# Termocouple.net
KiCad netlist of a schematic drawn in EAGLE
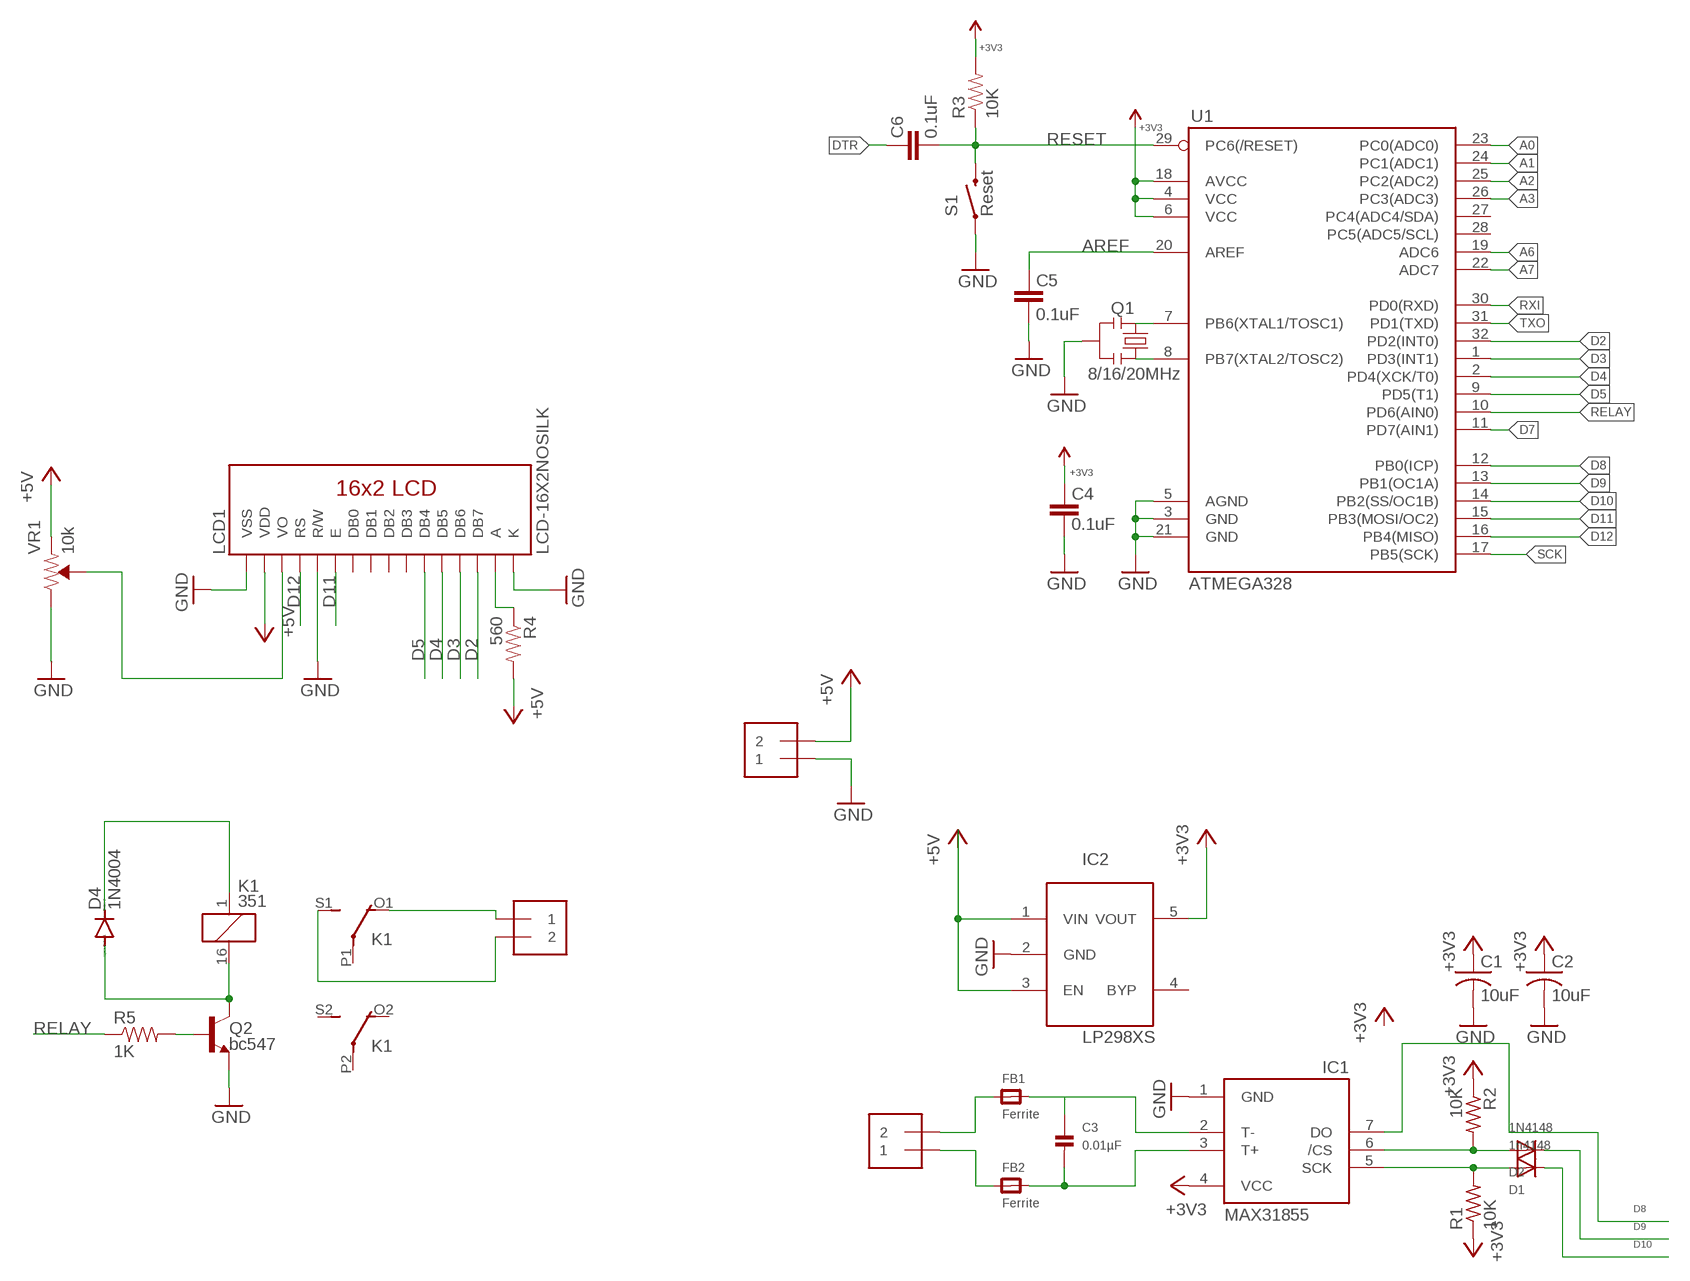
[diagram p0: schematic, sheet 1]

(export (version "E")
  (design (tool "Eeschema 10.0.6"))
  (components
    (comp (ref "C1")
      (value "10uF")
      (footprint "eagle-import:C0805K")
      (libsource (lib "eagle-import") (part "C-USC0805K"))
    )
    (comp (ref "C2")
      (value "10uF")
      (footprint "eagle-import:C0805K")
      (libsource (lib "eagle-import") (part "C-USC0805K"))
    )
    (comp (ref "C3")
      (value "0.01µF")
      (footprint "eagle-import:_0805")
      (libsource (lib "eagle-import") (part "CAP_CERAMIC_0805"))
    )
    (comp (ref "C4")
      (value "0.1uF")
      (footprint "eagle-import:0603-CAP")
      (libsource (lib "eagle-import") (part "CAP0603-CAP"))
    )
    (comp (ref "C5")
      (value "0.1uF")
      (footprint "eagle-import:0603-CAP")
      (libsource (lib "eagle-import") (part "CAP0603-CAP"))
    )
    (comp (ref "C6")
      (value "0.1uF")
      (footprint "eagle-import:0603-CAP")
      (libsource (lib "eagle-import") (part "CAP0603-CAP"))
    )
    (comp (ref "D1")
      (value "1n4148")
      (footprint "eagle-import:SOD-323F")
      (libsource (lib "eagle-import") (part "DIODESOD-323F"))
    )
    (comp (ref "D2")
      (value "1N4148")
      (footprint "eagle-import:SOD-323F")
      (libsource (lib "eagle-import") (part "DIODESOD-323F"))
    )
    (comp (ref "D4")
      (value "1N4004")
      (footprint "eagle-import:DO41-10")
      (libsource (lib "eagle-import") (part "1N4004"))
    )
    (comp (ref "FB1")
      (value "Ferrite")
      (footprint "eagle-import:_0805")
      (libsource (lib "eagle-import") (part "FERRITE_0805"))
    )
    (comp (ref "FB2")
      (value "Ferrite")
      (footprint "eagle-import:_0805")
      (libsource (lib "eagle-import") (part "FERRITE_0805"))
    )
    (comp (ref "IC1")
      (value "MAX31855")
      (footprint "eagle-import:SO08")
      (libsource (lib "eagle-import") (part "MAX6675"))
    )
    (comp (ref "IC2")
      (value "LP298XS")
      (footprint "eagle-import:SOT23-5L")
      (libsource (lib "eagle-import") (part "LP298XS"))
    )
    (comp (ref "J1")
      (value "1X2-3.5MM")
      (footprint "eagle-import:1X2-3.5MM")
      (libsource (lib "eagle-import") (part "1X2-3.5MM"))
    )
    (comp (ref "J2")
      (value "1X2-3.5MM")
      (footprint "eagle-import:1X2-3.5MM")
      (libsource (lib "eagle-import") (part "1X2-3.5MM"))
    )
    (comp (ref "J3")
      (value "1X2-3.5MM")
      (footprint "eagle-import:1X2-3.5MM")
      (libsource (lib "eagle-import") (part "1X2-3.5MM"))
    )
    (comp (ref "K1")
      (value "351")
      (footprint "eagle-import:351")
      (libsource (lib "eagle-import") (part "351"))
    )
    (comp (ref "LCD1")
      (value "LCD-16X2NOSILK")
      (footprint "eagle-import:LCD-16X2_NOSILK")
      (libsource (lib "eagle-import") (part "LCD-16X2NOSILK"))
    )
    (comp (ref "Q1")
      (value "8/16/20MHz")
      (footprint "eagle-import:RESONATOR-SMD-1_1")
      (libsource (lib "eagle-import") (part "RESONATOR1{colon}1"))
    )
    (comp (ref "Q2")
      (value "bc547")
      (footprint "eagle-import:SOT23-3")
      (libsource (lib "eagle-import") (part "TRANS_NPN-MMBT2222AL"))
    )
    (comp (ref "R1")
      (value "10K")
      (footprint "eagle-import:R0805")
      (libsource (lib "eagle-import") (part "R-US_R0805"))
    )
    (comp (ref "R2")
      (value "10K")
      (footprint "eagle-import:R0805")
      (libsource (lib "eagle-import") (part "R-US_R0805"))
    )
    (comp (ref "R3")
      (value "10K")
      (footprint "eagle-import:0805")
      (libsource (lib "eagle-import") (part "RESISTOR0805-RES"))
    )
    (comp (ref "R4")
      (value "560")
      (footprint "eagle-import:0805")
      (libsource (lib "eagle-import") (part "RESISTOR0805-RES"))
    )
    (comp (ref "R5")
      (value "1K")
      (footprint "eagle-import:0805")
      (libsource (lib "eagle-import") (part "RESISTOR0805-RES"))
    )
    (comp (ref "S1")
      (value "Reset")
      (footprint "eagle-import:TACTILE-SWITCH-SMD-ALT01")
      (libsource (lib "eagle-import") (part "SWITCH-MOMENTARY-2SMD-ALT01"))
    )
    (comp (ref "U1")
      (value "ATMEGA328")
      (footprint "eagle-import:TQFP32-08")
      (libsource (lib "eagle-import") (part "ATMEGA168"))
    )
    (comp (ref "VR1")
      (value "10k")
      (footprint "eagle-import:TRIMPOT-SMD-3MM-CLOSED")
      (libsource (lib "eagle-import") (part "TRIMPOT-SMD-3MM-CLOSED-1/8W-20%"))
    )
  )
  (nets
    (net (code "1") (name "+3V3") (class "Default")
      (node (ref "C1") (pin "1") (pinfunction "1_1") (pintype "passive"))
      (node (ref "C2") (pin "1") (pinfunction "1_1") (pintype "passive"))
      (node (ref "C4") (pin "2") (pinfunction "2_2") (pintype "passive"))
      (node (ref "IC1") (pin "4") (pinfunction "VCC_4") (pintype "power_in"))
      (node (ref "IC2") (pin "5") (pinfunction "VOUT_5") (pintype "bidirectional"))
      (node (ref "R1") (pin "1") (pinfunction "1_1") (pintype "passive"))
      (node (ref "R2") (pin "1") (pinfunction "1_1") (pintype "passive"))
      (node (ref "R3") (pin "2") (pinfunction "2_2") (pintype "passive"))
      (node (ref "U1") (pin "18") (pinfunction "AVCC_18") (pintype "bidirectional"))
      (node (ref "U1") (pin "4") (pinfunction "VCC_4") (pintype "bidirectional"))
      (node (ref "U1") (pin "6") (pinfunction "VCC_6") (pintype "bidirectional"))
    )
    (net (code "2") (name "+5V") (class "Default")
      (node (ref "IC2") (pin "1") (pinfunction "VIN_1") (pintype "bidirectional"))
      (node (ref "IC2") (pin "3") (pinfunction "EN_3") (pintype "bidirectional"))
      (node (ref "J2") (pin "2") (pinfunction "2_2") (pintype "passive"))
      (node (ref "LCD1") (pin "2") (pinfunction "VDD_2") (pintype "power_in"))
      (node (ref "R4") (pin "2") (pinfunction "2_2") (pintype "passive"))
      (node (ref "VR1") (pin "1") (pinfunction "CCW_1") (pintype "passive"))
    )
    (net (code "3") (name "/AREF") (class "Default")
      (node (ref "C5") (pin "2") (pinfunction "2_2") (pintype "passive"))
      (node (ref "U1") (pin "20") (pinfunction "AREF_20") (pintype "bidirectional"))
    )
    (net (code "4") (name "/RESET") (class "Default")
      (node (ref "C6") (pin "1") (pinfunction "1_1") (pintype "passive"))
      (node (ref "R3") (pin "1") (pinfunction "1_1") (pintype "passive"))
      (node (ref "S1") (pin "3") (pinfunction "2_3") (pintype "passive"))
      (node (ref "S1") (pin "4") (pinfunction "2_4") (pintype "passive"))
      (node (ref "U1") (pin "29") (pinfunction "PC6(/RESET)_29") (pintype "bidirectional"))
    )
    (net (code "5") (name "A0") (class "Default")
      (node (ref "U1") (pin "23") (pinfunction "PC0(ADC0)_23") (pintype "bidirectional"))
    )
    (net (code "6") (name "A1") (class "Default")
      (node (ref "U1") (pin "24") (pinfunction "PC1(ADC1)_24") (pintype "bidirectional"))
    )
    (net (code "7") (name "A2") (class "Default")
      (node (ref "U1") (pin "25") (pinfunction "PC2(ADC2)_25") (pintype "bidirectional"))
    )
    (net (code "8") (name "A3") (class "Default")
      (node (ref "U1") (pin "26") (pinfunction "PC3(ADC3)_26") (pintype "bidirectional"))
    )
    (net (code "9") (name "A6") (class "Default")
      (node (ref "U1") (pin "19") (pinfunction "ADC6_19") (pintype "bidirectional"))
    )
    (net (code "10") (name "A7") (class "Default")
      (node (ref "U1") (pin "22") (pinfunction "ADC7_22") (pintype "bidirectional"))
    )
    (net (code "11") (name "D2") (class "Default")
      (node (ref "LCD1") (pin "14") (pinfunction "DB7_14") (pintype "bidirectional"))
      (node (ref "U1") (pin "32") (pinfunction "PD2(INT0)_32") (pintype "bidirectional"))
    )
    (net (code "12") (name "D3") (class "Default")
      (node (ref "LCD1") (pin "13") (pinfunction "DB6_13") (pintype "bidirectional"))
      (node (ref "U1") (pin "1") (pinfunction "PD3(INT1)_1") (pintype "bidirectional"))
    )
    (net (code "13") (name "D4") (class "Default")
      (node (ref "LCD1") (pin "12") (pinfunction "DB5_12") (pintype "bidirectional"))
      (node (ref "U1") (pin "2") (pinfunction "PD4(XCK/T0)_2") (pintype "bidirectional"))
    )
    (net (code "14") (name "D5") (class "Default")
      (node (ref "LCD1") (pin "11") (pinfunction "DB4_11") (pintype "bidirectional"))
      (node (ref "U1") (pin "9") (pinfunction "PD5(T1)_9") (pintype "bidirectional"))
    )
    (net (code "15") (name "D7") (class "Default")
      (node (ref "U1") (pin "11") (pinfunction "PD7(AIN1)_11") (pintype "bidirectional"))
    )
    (net (code "16") (name "D8") (class "Default")
      (node (ref "IC1") (pin "7") (pinfunction "DO_7") (pintype "output"))
      (node (ref "U1") (pin "12") (pinfunction "PB0(ICP)_12") (pintype "bidirectional"))
    )
    (net (code "17") (name "D9") (class "Default")
      (node (ref "D2") (pin "C") (pinfunction "C_C") (pintype "passive"))
      (node (ref "U1") (pin "13") (pinfunction "PB1(OC1A)_13") (pintype "bidirectional"))
    )
    (net (code "18") (name "D10") (class "Default")
      (node (ref "D1") (pin "C") (pinfunction "C_C") (pintype "passive"))
      (node (ref "U1") (pin "14") (pinfunction "PB2(SS/OC1B)_14") (pintype "bidirectional"))
    )
    (net (code "19") (name "D11") (class "Default")
      (node (ref "LCD1") (pin "6") (pinfunction "E_6") (pintype "input"))
      (node (ref "U1") (pin "15") (pinfunction "PB3(MOSI/OC2)_15") (pintype "bidirectional"))
    )
    (net (code "20") (name "D12") (class "Default")
      (node (ref "LCD1") (pin "4") (pinfunction "RS_4") (pintype "input"))
      (node (ref "U1") (pin "16") (pinfunction "PB4(MISO)_16") (pintype "bidirectional"))
    )
    (net (code "21") (name "DTR") (class "Default")
      (node (ref "C6") (pin "2") (pinfunction "2_2") (pintype "passive"))
    )
    (net (code "22") (name "GND") (class "Default")
      (node (ref "C1") (pin "2") (pinfunction "2_2") (pintype "passive"))
      (node (ref "C2") (pin "2") (pinfunction "2_2") (pintype "passive"))
      (node (ref "C4") (pin "1") (pinfunction "1_1") (pintype "passive"))
      (node (ref "C5") (pin "1") (pinfunction "1_1") (pintype "passive"))
      (node (ref "IC1") (pin "1") (pinfunction "GND_1") (pintype "power_in"))
      (node (ref "IC2") (pin "2") (pinfunction "GND_2") (pintype "bidirectional"))
      (node (ref "J2") (pin "1") (pinfunction "1_1") (pintype "passive"))
      (node (ref "LCD1") (pin "1") (pinfunction "VSS_1") (pintype "power_in"))
      (node (ref "LCD1") (pin "16") (pinfunction "K_16") (pintype "power_in"))
      (node (ref "LCD1") (pin "5") (pinfunction "R/W_5") (pintype "input"))
      (node (ref "Q1") (pin "2") (pinfunction "2_2") (pintype "passive"))
      (node (ref "Q2") (pin "2") (pinfunction "E_2") (pintype "passive"))
      (node (ref "S1") (pin "1") (pinfunction "1_1") (pintype "passive"))
      (node (ref "S1") (pin "2") (pinfunction "1_2") (pintype "passive"))
      (node (ref "U1") (pin "21") (pinfunction "GND_21") (pintype "bidirectional"))
      (node (ref "U1") (pin "3") (pinfunction "GND_3") (pintype "bidirectional"))
      (node (ref "U1") (pin "5") (pinfunction "AGND_5") (pintype "bidirectional"))
      (node (ref "VR1") (pin "3") (pinfunction "CW_3") (pintype "passive"))
    )
    (net (code "23") (name "Net-(C3-P$1)") (class "Default")
      (node (ref "C3") (pin "1") (pinfunction "P$1_1") (pintype "passive"))
      (node (ref "FB1") (pin "2") (pinfunction "P$2_2") (pintype "passive"))
      (node (ref "IC1") (pin "2") (pinfunction "T-_2") (pintype "input"))
    )
    (net (code "24") (name "Net-(C3-P$2)") (class "Default")
      (node (ref "C3") (pin "2") (pinfunction "P$2_2") (pintype "passive"))
      (node (ref "FB2") (pin "2") (pinfunction "P$2_2") (pintype "passive"))
      (node (ref "IC1") (pin "3") (pinfunction "T+_3") (pintype "input"))
    )
    (net (code "25") (name "Net-(D4-PadC)") (class "Default")
      (node (ref "D4") (pin "C") (pinfunction "C_C") (pintype "passive"))
      (node (ref "K1") (pin "1") (pinfunction "1_1") (pintype "passive"))
    )
    (net (code "26") (name "Net-(FB1-P$1)") (class "Default")
      (node (ref "FB1") (pin "1") (pinfunction "P$1_1") (pintype "passive"))
      (node (ref "J1") (pin "2") (pinfunction "2_2") (pintype "passive"))
    )
    (net (code "27") (name "Net-(FB2-P$1)") (class "Default")
      (node (ref "FB2") (pin "1") (pinfunction "P$1_1") (pintype "passive"))
      (node (ref "J1") (pin "1") (pinfunction "1_1") (pintype "passive"))
    )
    (net (code "28") (name "Net-(IC1-{slash}CS)") (class "Default")
      (node (ref "D2") (pin "A") (pinfunction "A_A") (pintype "passive"))
      (node (ref "IC1") (pin "6") (pinfunction "/CS_6") (pintype "input"))
      (node (ref "R2") (pin "2") (pinfunction "2_2") (pintype "passive"))
    )
    (net (code "29") (name "Net-(K1A-2)") (class "Default")
      (node (ref "D4") (pin "A") (pinfunction "A_A") (pintype "passive"))
      (node (ref "K1") (pin "16") (pinfunction "2_16") (pintype "passive"))
      (node (ref "Q2") (pin "3") (pinfunction "C_3") (pintype "passive"))
    )
    (net (code "30") (name "Net-(K1B-O)") (class "Default")
      (node (ref "J3") (pin "1") (pinfunction "1_1") (pintype "passive"))
      (node (ref "K1") (pin "O1") (pinfunction "O_O1") (pintype "passive"))
    )
    (net (code "31") (name "Net-(K1B-S)") (class "Default")
      (node (ref "J3") (pin "2") (pinfunction "2_2") (pintype "passive"))
      (node (ref "K1") (pin "S1") (pinfunction "S_S1") (pintype "passive"))
    )
    (net (code "32") (name "Net-(LCD1-A)") (class "Default")
      (node (ref "LCD1") (pin "15") (pinfunction "A_15") (pintype "power_in"))
      (node (ref "R4") (pin "1") (pinfunction "1_1") (pintype "passive"))
    )
    (net (code "33") (name "Net-(LCD1-VO)") (class "Default")
      (node (ref "LCD1") (pin "3") (pinfunction "VO_3") (pintype "bidirectional"))
      (node (ref "VR1") (pin "2") (pinfunction "WIPER_2") (pintype "passive"))
    )
    (net (code "34") (name "Net-(Q2-B)") (class "Default")
      (node (ref "Q2") (pin "1") (pinfunction "B_1") (pintype "passive"))
      (node (ref "R5") (pin "2") (pinfunction "2_2") (pintype "passive"))
    )
    (net (code "35") (name "Net-(U1-PB6(XTAL1{slash}TOSC1))") (class "Default")
      (node (ref "Q1") (pin "1") (pinfunction "1_1") (pintype "passive"))
      (node (ref "U1") (pin "7") (pinfunction "PB6(XTAL1/TOSC1)_7") (pintype "bidirectional"))
    )
    (net (code "36") (name "Net-(U1-PB7(XTAL2{slash}TOSC2))") (class "Default")
      (node (ref "Q1") (pin "3") (pinfunction "3_3") (pintype "passive"))
      (node (ref "U1") (pin "8") (pinfunction "PB7(XTAL2/TOSC2)_8") (pintype "bidirectional"))
    )
    (net (code "37") (name "RELAY") (class "Default")
      (node (ref "R5") (pin "1") (pinfunction "1_1") (pintype "passive"))
      (node (ref "U1") (pin "10") (pinfunction "PD6(AIN0)_10") (pintype "bidirectional"))
    )
    (net (code "38") (name "RXI") (class "Default")
      (node (ref "U1") (pin "30") (pinfunction "PD0(RXD)_30") (pintype "bidirectional"))
    )
    (net (code "39") (name "SCK") (class "Default")
      (node (ref "D1") (pin "A") (pinfunction "A_A") (pintype "passive"))
      (node (ref "IC1") (pin "5") (pinfunction "SCK_5") (pintype "input"))
      (node (ref "R1") (pin "2") (pinfunction "2_2") (pintype "passive"))
      (node (ref "U1") (pin "17") (pinfunction "PB5(SCK)_17") (pintype "bidirectional"))
    )
    (net (code "40") (name "TXO") (class "Default")
      (node (ref "U1") (pin "31") (pinfunction "PD1(TXD)_31") (pintype "bidirectional"))
    )
    (net (code "41") (name "unconnected-(IC2-BYP-Pad4)") (class "Default")
      (node (ref "IC2") (pin "4") (pinfunction "BYP_4") (pintype "bidirectional"))
    )
    (net (code "42") (name "unconnected-(K1B-P-PadP1)") (class "Default")
      (node (ref "K1") (pin "P1") (pinfunction "P_P1") (pintype "passive"))
    )
    (net (code "43") (name "unconnected-(K1C-O-PadO2)") (class "Default")
      (node (ref "K1") (pin "O2") (pinfunction "O_O2") (pintype "passive"))
    )
    (net (code "44") (name "unconnected-(K1C-P-PadP2)") (class "Default")
      (node (ref "K1") (pin "P2") (pinfunction "P_P2") (pintype "passive"))
    )
    (net (code "45") (name "unconnected-(K1C-S-PadS2)") (class "Default")
      (node (ref "K1") (pin "S2") (pinfunction "S_S2") (pintype "passive"))
    )
    (net (code "46") (name "unconnected-(LCD1-DB0-Pad7)") (class "Default")
      (node (ref "LCD1") (pin "7") (pinfunction "DB0_7") (pintype "bidirectional"))
    )
    (net (code "47") (name "unconnected-(LCD1-DB1-Pad8)") (class "Default")
      (node (ref "LCD1") (pin "8") (pinfunction "DB1_8") (pintype "bidirectional"))
    )
    (net (code "48") (name "unconnected-(LCD1-DB2-Pad9)") (class "Default")
      (node (ref "LCD1") (pin "9") (pinfunction "DB2_9") (pintype "bidirectional"))
    )
    (net (code "49") (name "unconnected-(LCD1-DB3-Pad10)") (class "Default")
      (node (ref "LCD1") (pin "10") (pinfunction "DB3_10") (pintype "bidirectional"))
    )
    (net (code "50") (name "unconnected-(U1-PC4(ADC4{slash}SDA)-Pad27)") (class "Default")
      (node (ref "U1") (pin "27") (pinfunction "PC4(ADC4/SDA)_27") (pintype "bidirectional"))
    )
    (net (code "51") (name "unconnected-(U1-PC5(ADC5{slash}SCL)-Pad28)") (class "Default")
      (node (ref "U1") (pin "28") (pinfunction "PC5(ADC5/SCL)_28") (pintype "bidirectional"))
    )
  )
)
